# OSO-MISC-20-009_Power_Adapter_for_Sensor.net
KiCad netlist of a schematic drawn in EAGLE
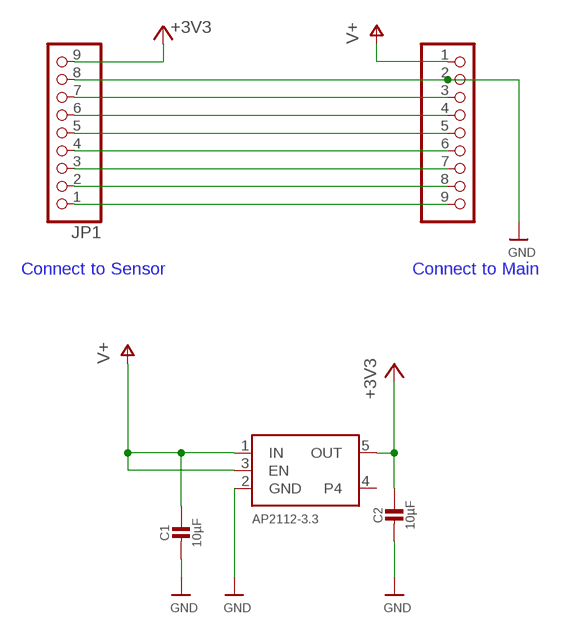
[diagram p0: schematic, sheet 1]

(export (version "E")
  (design (tool "Eeschema 10.0.6"))
  (components
    (comp (ref "C1")
      (value "10µF")
      (footprint "eagle-import:0805-NO")
      (libsource (lib "eagle-import") (part "CAP_CERAMIC0805-NOOUTLINE"))
    )
    (comp (ref "C2")
      (value "10µF")
      (footprint "eagle-import:0805-NO")
      (libsource (lib "eagle-import") (part "CAP_CERAMIC0805-NOOUTLINE"))
    )
    (comp (ref "JP1")
      (value "HEADER-1X9_JSTSH")
      (footprint "eagle-import:JST_SH9")
      (libsource (lib "eagle-import") (part "HEADER-1X9_JSTSH"))
    )
    (comp (ref "JP2")
      (value "HEADER-1X9_JSTSH")
      (footprint "eagle-import:JST_SH9")
      (libsource (lib "eagle-import") (part "HEADER-1X9_JSTSH"))
    )
    (comp (ref "U1")
      (value "AP2112-3.3")
      (footprint "eagle-import:SOT23-5")
      (libsource (lib "eagle-import") (part "VREG_SOT23-5"))
    )
  )
  (nets
    (net (code "1") (name "+3V3") (class "Default")
      (node (ref "C2") (pin "1") (pinfunction "1_1") (pintype "passive"))
      (node (ref "JP1") (pin "9") (pinfunction "9_9") (pintype "passive"))
      (node (ref "U1") (pin "5") (pinfunction "OUT_5") (pintype "power_in"))
    )
    (net (code "2") (name "GND") (class "Default")
      (node (ref "C1") (pin "2") (pinfunction "2_2") (pintype "passive"))
      (node (ref "C2") (pin "2") (pinfunction "2_2") (pintype "passive"))
      (node (ref "JP1") (pin "8") (pinfunction "8_8") (pintype "passive"))
      (node (ref "JP2") (pin "2") (pinfunction "2_2") (pintype "passive"))
      (node (ref "U1") (pin "2") (pinfunction "GND_2") (pintype "power_in"))
    )
    (net (code "3") (name "Net-(JP1-Pad1)") (class "Default")
      (node (ref "JP1") (pin "1") (pinfunction "1_1") (pintype "passive"))
      (node (ref "JP2") (pin "9") (pinfunction "9_9") (pintype "passive"))
    )
    (net (code "4") (name "Net-(JP1-Pad2)") (class "Default")
      (node (ref "JP1") (pin "2") (pinfunction "2_2") (pintype "passive"))
      (node (ref "JP2") (pin "8") (pinfunction "8_8") (pintype "passive"))
    )
    (net (code "5") (name "Net-(JP1-Pad3)") (class "Default")
      (node (ref "JP1") (pin "3") (pinfunction "3_3") (pintype "passive"))
      (node (ref "JP2") (pin "7") (pinfunction "7_7") (pintype "passive"))
    )
    (net (code "6") (name "Net-(JP1-Pad4)") (class "Default")
      (node (ref "JP1") (pin "4") (pinfunction "4_4") (pintype "passive"))
      (node (ref "JP2") (pin "6") (pinfunction "6_6") (pintype "passive"))
    )
    (net (code "7") (name "Net-(JP1-Pad5)") (class "Default")
      (node (ref "JP1") (pin "5") (pinfunction "5_5") (pintype "passive"))
      (node (ref "JP2") (pin "5") (pinfunction "5_5") (pintype "passive"))
    )
    (net (code "8") (name "Net-(JP1-Pad6)") (class "Default")
      (node (ref "JP1") (pin "6") (pinfunction "6_6") (pintype "passive"))
      (node (ref "JP2") (pin "4") (pinfunction "4_4") (pintype "passive"))
    )
    (net (code "9") (name "Net-(JP1-Pad7)") (class "Default")
      (node (ref "JP1") (pin "7") (pinfunction "7_7") (pintype "passive"))
      (node (ref "JP2") (pin "3") (pinfunction "3_3") (pintype "passive"))
    )
    (net (code "10") (name "V+") (class "Default")
      (node (ref "C1") (pin "1") (pinfunction "1_1") (pintype "passive"))
      (node (ref "JP2") (pin "1") (pinfunction "1_1") (pintype "passive"))
      (node (ref "U1") (pin "1") (pinfunction "IN_1") (pintype "power_in"))
      (node (ref "U1") (pin "3") (pinfunction "EN_3") (pintype "input"))
    )
    (net (code "11") (name "unconnected-(U1-P4-Pad4)") (class "Default")
      (node (ref "U1") (pin "4") (pinfunction "P4_4") (pintype "bidirectional"))
    )
  )
)
